# NixieAdapterIN14.net
KiCad netlist of a schematic drawn in Altium Designer
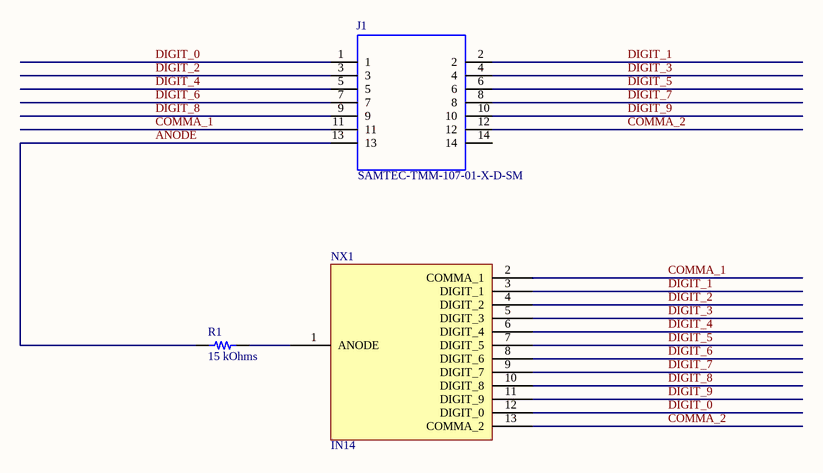
[diagram p0: NixieAdapterIN14.SchDoc]

(export (version "E")
  (design (tool "Eeschema 10.0.6"))
  (components
    (comp (ref "J1")
      (value "SAMTEC-TMM-107-01-X-D-SM")
      (footprint "SAMTEC-TMM-107-01-X-D-SM")
      (libsource (lib "SAMTEC-TMM-107-01-X-D-SM") (part "SAMTEC-TMM-107-01-X-D-SM"))
    )
    (comp (ref "NX1")
      (value "IN14")
      (footprint "IN-14 Nixie Tube")
      (description "IN-14 Nixie Tube")
      (libsource (lib "IN14") (part "IN14"))
    )
    (comp (ref "R1")
      (value "15 kOhms")
      (footprint "RES 0805_2012")
      (description "RES SMD 15K OHM 1% 1/2W 0805")
      (fields (field (name "PART NUMBER") "CRCW080515K0FKEAHP") (field (name "MANUFACTURER") "Vishay Dale"))
      (libsource (lib "Celestial Altium Library - altium_library") (part "Resistor"))
    )
  )
  (nets
    (net (code "1") (name "/ANODE") (class "Default")
      (node (ref "J1") (pin "13") (pinfunction "13_13") (pintype "passive"))
      (node (ref "R1") (pin "1") (pinfunction "1_1") (pintype "passive"))
    )
    (net (code "2") (name "/COMMA_1") (class "Default")
      (node (ref "J1") (pin "11") (pinfunction "11_11") (pintype "passive"))
      (node (ref "NX1") (pin "2") (pinfunction "COMMA_1_2") (pintype "passive"))
    )
    (net (code "3") (name "/COMMA_2") (class "Default")
      (node (ref "J1") (pin "12") (pinfunction "12_12") (pintype "passive"))
      (node (ref "NX1") (pin "13") (pinfunction "COMMA_2_13") (pintype "passive"))
    )
    (net (code "4") (name "/DIGIT_0") (class "Default")
      (node (ref "J1") (pin "1") (pinfunction "1_1") (pintype "passive"))
      (node (ref "NX1") (pin "12") (pinfunction "DIGIT_0_12") (pintype "passive"))
    )
    (net (code "5") (name "/DIGIT_1") (class "Default")
      (node (ref "J1") (pin "2") (pinfunction "2_2") (pintype "passive"))
      (node (ref "NX1") (pin "3") (pinfunction "DIGIT_1_3") (pintype "passive"))
    )
    (net (code "6") (name "/DIGIT_2") (class "Default")
      (node (ref "J1") (pin "3") (pinfunction "3_3") (pintype "passive"))
      (node (ref "NX1") (pin "4") (pinfunction "DIGIT_2_4") (pintype "passive"))
    )
    (net (code "7") (name "/DIGIT_3") (class "Default")
      (node (ref "J1") (pin "4") (pinfunction "4_4") (pintype "passive"))
      (node (ref "NX1") (pin "5") (pinfunction "DIGIT_3_5") (pintype "passive"))
    )
    (net (code "8") (name "/DIGIT_4") (class "Default")
      (node (ref "J1") (pin "5") (pinfunction "5_5") (pintype "passive"))
      (node (ref "NX1") (pin "6") (pinfunction "DIGIT_4_6") (pintype "passive"))
    )
    (net (code "9") (name "/DIGIT_5") (class "Default")
      (node (ref "J1") (pin "6") (pinfunction "6_6") (pintype "passive"))
      (node (ref "NX1") (pin "7") (pinfunction "DIGIT_5_7") (pintype "passive"))
    )
    (net (code "10") (name "/DIGIT_6") (class "Default")
      (node (ref "J1") (pin "7") (pinfunction "7_7") (pintype "passive"))
      (node (ref "NX1") (pin "8") (pinfunction "DIGIT_6_8") (pintype "passive"))
    )
    (net (code "11") (name "/DIGIT_7") (class "Default")
      (node (ref "J1") (pin "8") (pinfunction "8_8") (pintype "passive"))
      (node (ref "NX1") (pin "9") (pinfunction "DIGIT_7_9") (pintype "passive"))
    )
    (net (code "12") (name "/DIGIT_8") (class "Default")
      (node (ref "J1") (pin "9") (pinfunction "9_9") (pintype "passive"))
      (node (ref "NX1") (pin "10") (pinfunction "DIGIT_8_10") (pintype "passive"))
    )
    (net (code "13") (name "/DIGIT_9") (class "Default")
      (node (ref "J1") (pin "10") (pinfunction "10_10") (pintype "passive"))
      (node (ref "NX1") (pin "11") (pinfunction "DIGIT_9_11") (pintype "passive"))
    )
    (net (code "14") (name "Net-(NX1-ANODE)") (class "Default")
      (node (ref "NX1") (pin "1") (pinfunction "ANODE_1") (pintype "passive"))
      (node (ref "R1") (pin "2") (pinfunction "2_2") (pintype "passive"))
    )
    (net (code "15") (name "unconnected-(J1-Pad14)") (class "Default")
      (node (ref "J1") (pin "14") (pinfunction "14_14") (pintype "passive"))
    )
  )
)
